# Eagle_final_project3.net
KiCad netlist of a schematic drawn in EAGLE
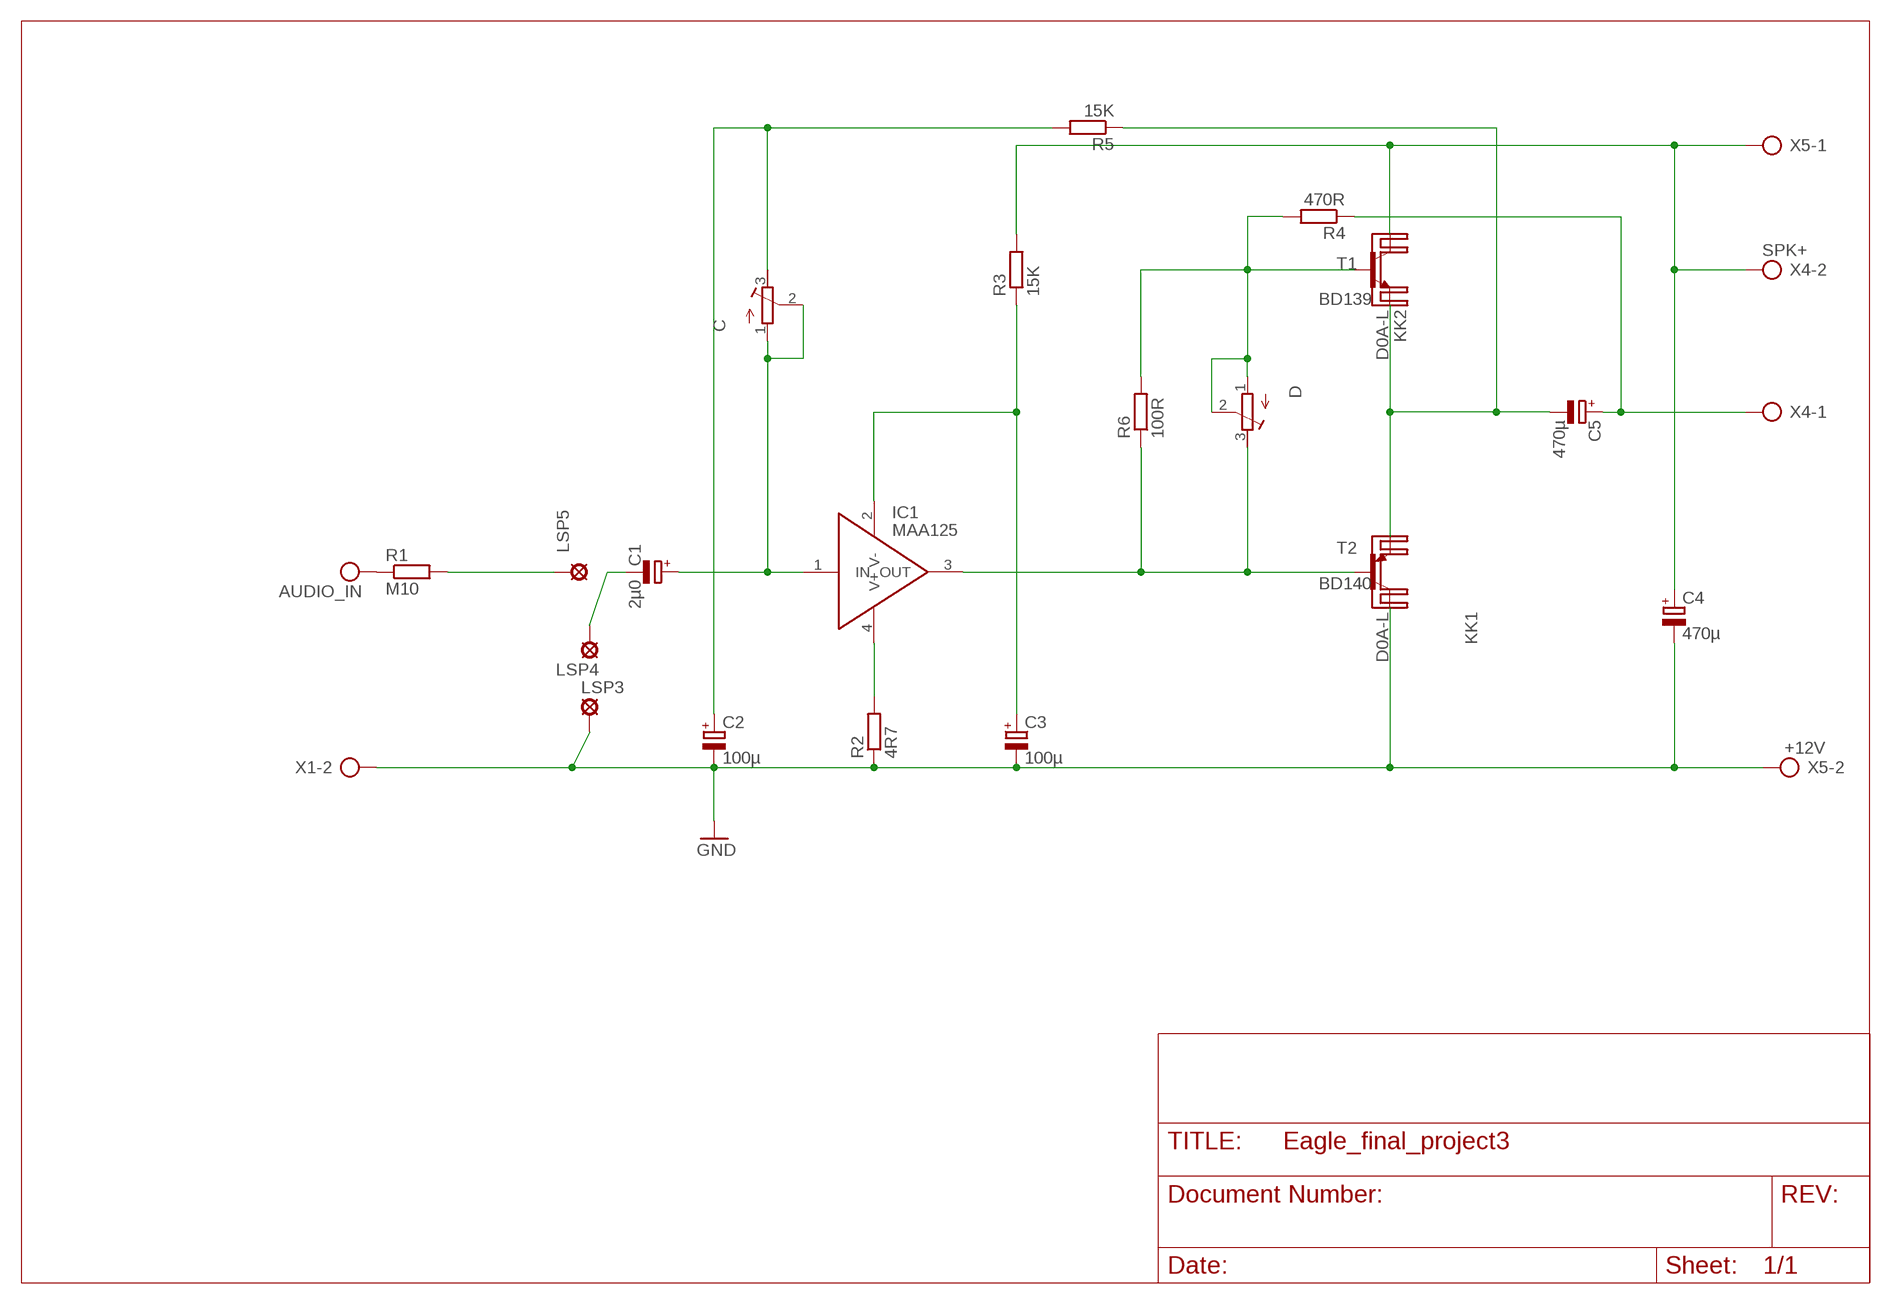
[diagram p0: schematic, sheet 1]

(export (version "E")
  (design (tool "Eeschema 10.0.6"))
  (components
    (comp (ref "C")
      (value "R-TRIMM3339P")
      (footprint "eagle-import:RTRIM3339P")
      (libsource (lib "eagle-import") (part "R-TRIMM3339P"))
    )
    (comp (ref "C1")
      (value "2µ0")
      (footprint "eagle-import:E2-5")
      (libsource (lib "eagle-import") (part "CPOL-EUE2-5"))
    )
    (comp (ref "C2")
      (value "100µ")
      (footprint "eagle-import:E2-5")
      (libsource (lib "eagle-import") (part "CPOL-EUE2-5"))
    )
    (comp (ref "C3")
      (value "100µ")
      (footprint "eagle-import:E2-5")
      (libsource (lib "eagle-import") (part "CPOL-EUE2-5"))
    )
    (comp (ref "C4")
      (value "470µ")
      (footprint "eagle-import:E2-5")
      (libsource (lib "eagle-import") (part "CPOL-EUE2-5"))
    )
    (comp (ref "C5")
      (value "470µ")
      (footprint "eagle-import:E2,5-6")
      (libsource (lib "eagle-import") (part "CPOL-EUE2.5-6"))
    )
    (comp (ref "D")
      (value "R-TRIMM3339P")
      (footprint "eagle-import:RTRIM3339P")
      (libsource (lib "eagle-import") (part "R-TRIMM3339P"))
    )
    (comp (ref "IC1")
      (value "MAA125")
      (footprint "eagle-import:IO-1")
      (libsource (lib "eagle-import") (part "MAA125"))
    )
    (comp (ref "KK1")
      (value "D0A-L")
      (footprint "eagle-import:D02A-L")
      (libsource (lib "eagle-import") (part "D0A-L"))
    )
    (comp (ref "KK2")
      (value "D0A-L")
      (footprint "eagle-import:D02A-L")
      (libsource (lib "eagle-import") (part "D0A-L"))
    )
    (comp (ref "LSP3")
      (value "LSP10")
      (footprint "eagle-import:LSP10")
      (libsource (lib "eagle-import") (part "LSP10"))
    )
    (comp (ref "LSP4")
      (value "LSP10")
      (footprint "eagle-import:LSP10")
      (libsource (lib "eagle-import") (part "LSP10"))
    )
    (comp (ref "LSP5")
      (value "LSP10")
      (footprint "eagle-import:LSP10")
      (libsource (lib "eagle-import") (part "LSP10"))
    )
    (comp (ref "Q1")
      (value "BD139")
      (footprint "eagle-import:TO126")
      (libsource (lib "eagle-import") (part "BD139"))
    )
    (comp (ref "R1")
      (value "M10")
      (footprint "eagle-import:0207_10")
      (libsource (lib "eagle-import") (part "R-EU_0207/10"))
    )
    (comp (ref "R2")
      (value "4R7")
      (footprint "eagle-import:0207_10")
      (libsource (lib "eagle-import") (part "R-EU_0207/10"))
    )
    (comp (ref "R3")
      (value "15K")
      (footprint "eagle-import:0207_10")
      (libsource (lib "eagle-import") (part "R-EU_0207/10"))
    )
    (comp (ref "R4")
      (value "470R")
      (footprint "eagle-import:0207_10")
      (libsource (lib "eagle-import") (part "R-EU_0207/10"))
    )
    (comp (ref "R5")
      (value "15K")
      (footprint "eagle-import:0207_10")
      (libsource (lib "eagle-import") (part "R-EU_0207/10"))
    )
    (comp (ref "R6")
      (value "100R")
      (footprint "eagle-import:0207_10")
      (libsource (lib "eagle-import") (part "R-EU_0207/10"))
    )
    (comp (ref "T2")
      (value "BD140")
      (footprint "eagle-import:TO126")
      (libsource (lib "eagle-import") (part "BD140"))
    )
    (comp (ref "X1")
      (value "AUDIO_IN")
      (footprint "eagle-import:AK300_2")
      (libsource (lib "eagle-import") (part "AK300/2"))
    )
    (comp (ref "X4")
      (value "SPK+")
      (footprint "eagle-import:AK300_2")
      (libsource (lib "eagle-import") (part "AK300/2"))
    )
    (comp (ref "X5")
      (value "+12V")
      (footprint "eagle-import:AK300_2")
      (libsource (lib "eagle-import") (part "AK300/2"))
    )
  )
  (nets
    (net (code "1") (name "/T1") (class "Default")
      (node (ref "D") (pin "1") (pinfunction "A_1") (pintype "passive"))
      (node (ref "D") (pin "2") (pinfunction "S_2") (pintype "passive"))
      (node (ref "Q1") (pin "3") (pinfunction "B_3") (pintype "passive"))
      (node (ref "R4") (pin "2") (pinfunction "2_2") (pintype "passive"))
      (node (ref "R6") (pin "2") (pinfunction "2_2") (pintype "passive"))
    )
    (net (code "2") (name "GND") (class "Default")
      (node (ref "C2") (pin "-") (pinfunction "-_-") (pintype "passive"))
      (node (ref "C3") (pin "-") (pinfunction "-_-") (pintype "passive"))
      (node (ref "C4") (pin "-") (pinfunction "-_-") (pintype "passive"))
      (node (ref "LSP3") (pin "MP") (pinfunction "MP_MP") (pintype "passive"))
      (node (ref "R2") (pin "1") (pinfunction "1_1") (pintype "passive"))
      (node (ref "T2") (pin "2") (pinfunction "C_2") (pintype "passive"))
      (node (ref "X1") (pin "2") (pinfunction "KL_2") (pintype "passive"))
      (node (ref "X5") (pin "2") (pinfunction "KL_2") (pintype "passive"))
    )
    (net (code "3") (name "Net-(C-A)") (class "Default")
      (node (ref "C") (pin "1") (pinfunction "A_1") (pintype "passive"))
      (node (ref "C") (pin "2") (pinfunction "S_2") (pintype "passive"))
      (node (ref "C1") (pin "+") (pinfunction "+_+") (pintype "passive"))
      (node (ref "IC1") (pin "1") (pinfunction "IN_1") (pintype "input"))
    )
    (net (code "4") (name "Net-(C-E)") (class "Default")
      (node (ref "C") (pin "3") (pinfunction "E_3") (pintype "passive"))
      (node (ref "C2") (pin "+") (pinfunction "+_+") (pintype "passive"))
      (node (ref "R5") (pin "2") (pinfunction "2_2") (pintype "passive"))
    )
    (net (code "5") (name "Net-(C1-Pad-)") (class "Default")
      (node (ref "C1") (pin "-") (pinfunction "-_-") (pintype "passive"))
      (node (ref "LSP4") (pin "MP") (pinfunction "MP_MP") (pintype "passive"))
    )
    (net (code "6") (name "Net-(D-E)") (class "Default")
      (node (ref "D") (pin "3") (pinfunction "E_3") (pintype "passive"))
      (node (ref "IC1") (pin "3") (pinfunction "OUT_3") (pintype "output"))
      (node (ref "R6") (pin "1") (pinfunction "1_1") (pintype "passive"))
      (node (ref "T2") (pin "3") (pinfunction "B_3") (pintype "passive"))
    )
    (net (code "7") (name "Net-(IC1-V+)") (class "Default")
      (node (ref "IC1") (pin "4") (pinfunction "V+_4") (pintype "power_in"))
      (node (ref "R2") (pin "2") (pinfunction "2_2") (pintype "passive"))
    )
    (net (code "8") (name "Net-(IC1-V-)") (class "Default")
      (node (ref "C3") (pin "+") (pinfunction "+_+") (pintype "passive"))
      (node (ref "IC1") (pin "2") (pinfunction "V-_2") (pintype "power_in"))
      (node (ref "R3") (pin "1") (pinfunction "1_1") (pintype "passive"))
    )
    (net (code "9") (name "Net-(LSP5-PadMP)") (class "Default")
      (node (ref "LSP5") (pin "MP") (pinfunction "MP_MP") (pintype "passive"))
      (node (ref "R1") (pin "2") (pinfunction "2_2") (pintype "passive"))
    )
    (net (code "10") (name "Net-(Q1-C)") (class "Default")
      (node (ref "C4") (pin "+") (pinfunction "+_+") (pintype "passive"))
      (node (ref "Q1") (pin "2") (pinfunction "C_2") (pintype "passive"))
      (node (ref "R3") (pin "2") (pinfunction "2_2") (pintype "passive"))
      (node (ref "X4") (pin "2") (pinfunction "KL_2") (pintype "passive"))
      (node (ref "X5") (pin "1") (pinfunction "KL_1") (pintype "passive"))
    )
    (net (code "11") (name "Net-(Q1-E)") (class "Default")
      (node (ref "C5") (pin "-") (pinfunction "-_-") (pintype "passive"))
      (node (ref "Q1") (pin "1") (pinfunction "E_1") (pintype "passive"))
      (node (ref "R5") (pin "1") (pinfunction "1_1") (pintype "passive"))
      (node (ref "T2") (pin "1") (pinfunction "E_1") (pintype "passive"))
    )
    (net (code "12") (name "Net-(X1A-KL)") (class "Default")
      (node (ref "R1") (pin "1") (pinfunction "1_1") (pintype "passive"))
      (node (ref "X1") (pin "1") (pinfunction "KL_1") (pintype "passive"))
    )
    (net (code "13") (name "Net-(X4A-KL)") (class "Default")
      (node (ref "C5") (pin "+") (pinfunction "+_+") (pintype "passive"))
      (node (ref "R4") (pin "1") (pinfunction "1_1") (pintype "passive"))
      (node (ref "X4") (pin "1") (pinfunction "KL_1") (pintype "passive"))
    )
  )
)
